# RK3562-DDR-PHY.net
KiCad netlist of a schematic drawn in Altium Designer
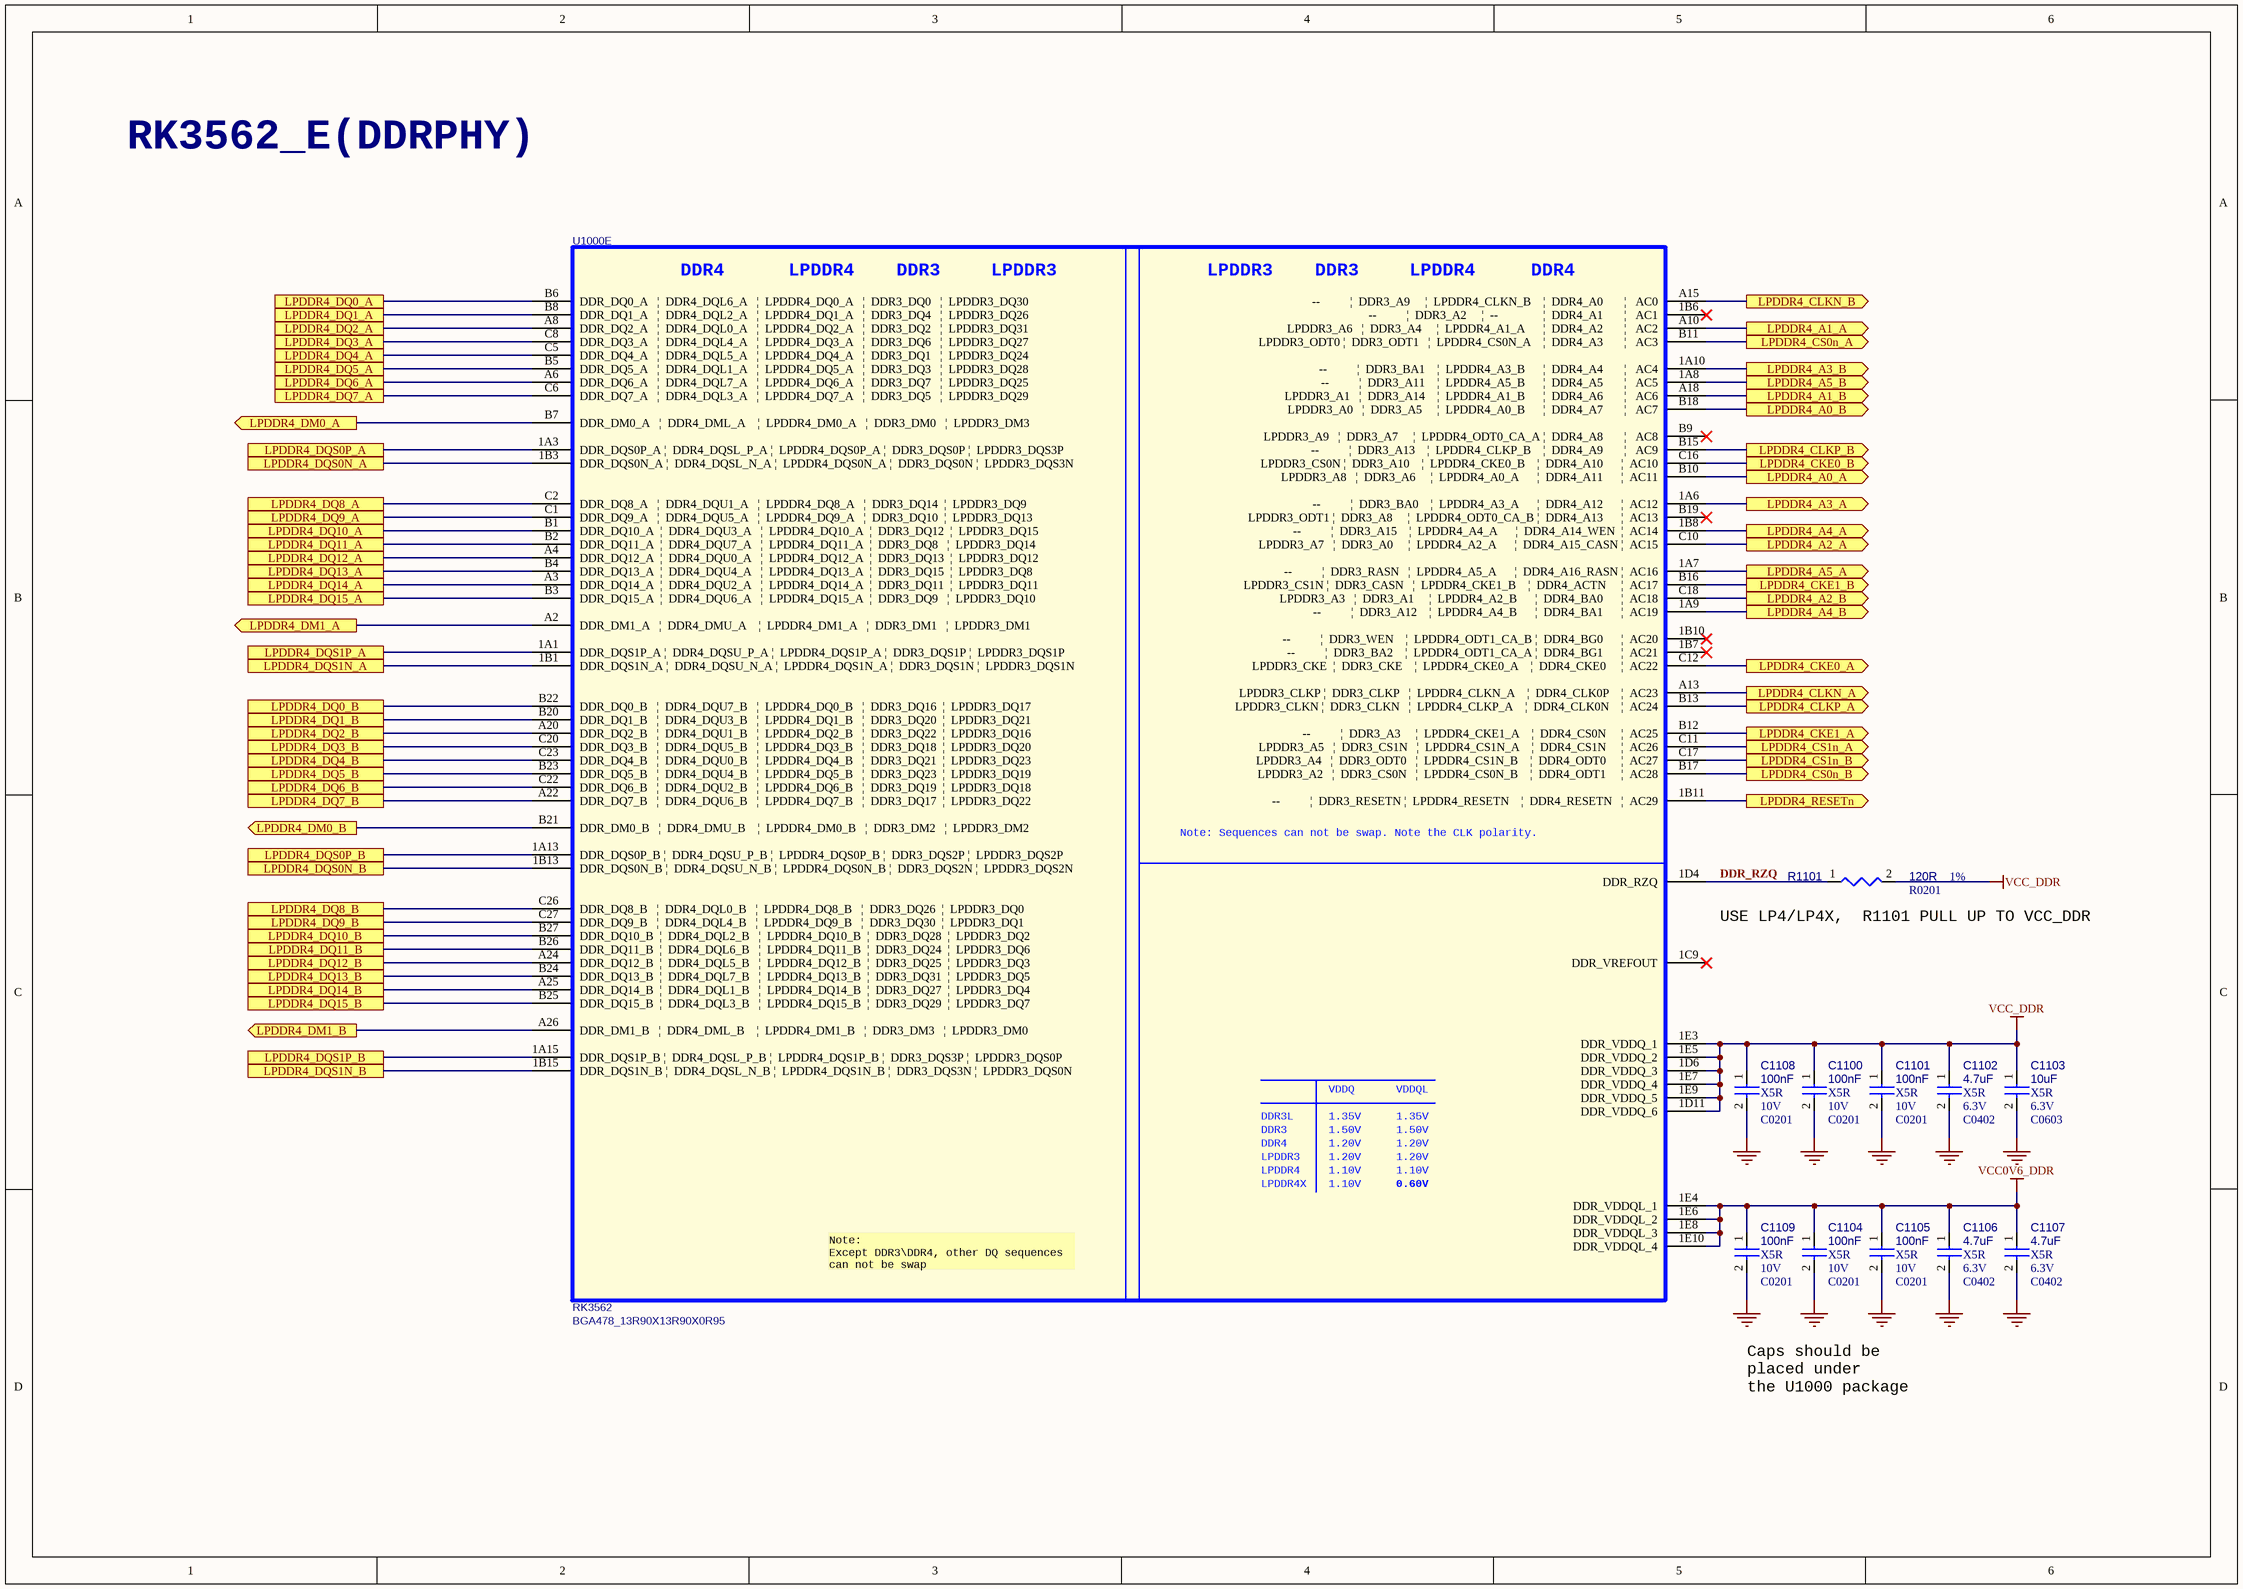
[diagram p0: RK3562-DDR-PHY.SchDoc]

(export (version "E")
  (design (tool "Eeschema 10.0.6"))
  (components
    (comp (ref "C1100")
      (value "100nF")
      (footprint "C0201")
      (description "cap,100.00nF,+/-10%,10V,X5R,C0201")
      (fields
        (field (name "DIELECTRIC") "X5R")
        (field (name "PCB FOOTPRINT") "C0201")
        (field (name "VOLTAGE") "10V")
        (field (name "MANUFACTURER") "TDK")
        (field (name "TOLERANCE") "10%")
        (field (name "CREATED BY") "JJJ")
      )
      (libsource (lib "RK3562_REF") (part "CAP NP"))
    )
    (comp (ref "C1101")
      (value "100nF")
      (footprint "C0201")
      (description "cap,100.00nF,+/-10%,10V,X5R,C0201")
      (fields
        (field (name "DIELECTRIC") "X5R")
        (field (name "PCB FOOTPRINT") "C0201")
        (field (name "VOLTAGE") "10V")
        (field (name "MANUFACTURER") "TDK")
        (field (name "TOLERANCE") "10%")
        (field (name "CREATED BY") "JJJ")
      )
      (libsource (lib "RK3562_REF") (part "CAP NP"))
    )
    (comp (ref "C1102")
      (value "4.7uF")
      (footprint "C0402")
      (description "cap,4.70uF,+/-10%,6.3V,X5R,C0402")
      (fields
        (field (name "DIELECTRIC") "X5R")
        (field (name "PCB FOOTPRINT") "C0402")
        (field (name "VOLTAGE") "6.3V")
        (field (name "TOLERANCE") "10%")
        (field (name "MANUFACTURER") "TDK")
        (field (name "CREATED BY") "JJJ")
      )
      (libsource (lib "RK3562_REF") (part "CAP NP"))
    )
    (comp (ref "C1103")
      (value "10uF")
      (footprint "C0603")
      (description "cap,10.00uF,+/-10%,6.3V,X5R,C0603")
      (fields
        (field (name "DIELECTRIC") "X5R")
        (field (name "PCB FOOTPRINT") "C0603")
        (field (name "VOLTAGE") "6.3V")
        (field (name "MANUFACTURER") "TDK")
        (field (name "TOLERANCE") "10%")
        (field (name "CREATED BY") "JJJ")
      )
      (libsource (lib "RK3562_REF") (part "CAP NP"))
    )
    (comp (ref "C1104")
      (value "100nF")
      (footprint "C0201")
      (description "cap,100.00nF,+/-10%,10V,X5R,C0201")
      (fields
        (field (name "DIELECTRIC") "X5R")
        (field (name "PCB FOOTPRINT") "C0201")
        (field (name "VOLTAGE") "10V")
        (field (name "MANUFACTURER") "TDK")
        (field (name "TOLERANCE") "10%")
        (field (name "CREATED BY") "JJJ")
      )
      (libsource (lib "RK3562_REF") (part "CAP NP"))
    )
    (comp (ref "C1105")
      (value "100nF")
      (footprint "C0201")
      (description "cap,100.00nF,+/-10%,10V,X5R,C0201")
      (fields
        (field (name "DIELECTRIC") "X5R")
        (field (name "PCB FOOTPRINT") "C0201")
        (field (name "VOLTAGE") "10V")
        (field (name "MANUFACTURER") "TDK")
        (field (name "TOLERANCE") "10%")
        (field (name "CREATED BY") "JJJ")
      )
      (libsource (lib "RK3562_REF") (part "CAP NP"))
    )
    (comp (ref "C1106")
      (value "4.7uF")
      (footprint "C0402")
      (description "cap,4.70uF,+/-10%,6.3V,X5R,C0402")
      (fields
        (field (name "DIELECTRIC") "X5R")
        (field (name "PCB FOOTPRINT") "C0402")
        (field (name "VOLTAGE") "6.3V")
        (field (name "TOLERANCE") "10%")
        (field (name "MANUFACTURER") "TDK")
        (field (name "CREATED BY") "JJJ")
      )
      (libsource (lib "RK3562_REF") (part "CAP NP"))
    )
    (comp (ref "C1107")
      (value "4.7uF")
      (footprint "C0402")
      (description "cap,4.70uF,+/-10%,6.3V,X5R,C0402")
      (fields
        (field (name "DIELECTRIC") "X5R")
        (field (name "PCB FOOTPRINT") "C0402")
        (field (name "VOLTAGE") "6.3V")
        (field (name "MANUFACTURER") "TDK")
        (field (name "TOLERANCE") "10%")
        (field (name "CREATED BY") "JJJ")
      )
      (libsource (lib "RK3562_REF") (part "CAP NP"))
    )
    (comp (ref "C1108")
      (value "100nF")
      (footprint "C0201")
      (description "cap,100.00nF,+/-10%,10V,X5R,C0201")
      (fields
        (field (name "DIELECTRIC") "X5R")
        (field (name "PCB FOOTPRINT") "C0201")
        (field (name "VOLTAGE") "10V")
        (field (name "TOLERANCE") "10%")
        (field (name "MANUFACTURER") "TDK")
        (field (name "CREATED BY") "JJJ")
      )
      (libsource (lib "RK3562_REF") (part "CAP NP"))
    )
    (comp (ref "C1109")
      (value "100nF")
      (footprint "C0201")
      (description "cap,100.00nF,+/-10%,10V,X5R,C0201")
      (fields
        (field (name "DIELECTRIC") "X5R")
        (field (name "PCB FOOTPRINT") "C0201")
        (field (name "VOLTAGE") "10V")
        (field (name "TOLERANCE") "10%")
        (field (name "MANUFACTURER") "TDK")
        (field (name "CREATED BY") "JJJ")
      )
      (libsource (lib "RK3562_REF") (part "CAP NP"))
    )
    (comp (ref "R1101")
      (value "120R")
      (footprint "R0201")
      (description "通用厚膜电阻,120R,+/-1%,R0201,1/20W.")
      (fields
        (field (name "TOLERANCE") "1%")
        (field (name "PCB FOOTPRINT") "R0201")
        (field (name "MANUFACTURER") "YAGEO")
        (field (name "CREATED BY") "YTL")
      )
      (libsource (lib "RK3562_REF") (part "RESISTOR"))
    )
    (comp (ref "U1000")
      (value "RK3562")
      (footprint "BGA478_13R90X13R90X0R95")
      (description "ROCKCHIP SOC")
      (fields
        (field (name "PCB FOOTPRINT") "BGA478_13R90X13R90X0R95")
        (field (name "MANUFACTURER") "Rockchip (瑞芯微)")
        (field (name "CREATED BY") "JJJ")
      )
      (libsource (lib "RK3562_REF") (part "SOC_RK3562"))
    )
  )
  (nets
    (net (code "1") (name "/DDR_RZQ") (class "Default")
      (node (ref "R1101") (pin "1") (pinfunction "1_1") (pintype "passive"))
      (node (ref "U1000") (pin "1D4") (pinfunction "DDR_RZQ_1D4") (pintype "passive"))
    )
    (net (code "2") (name "/LPDDR4_A0_A") (class "Default")
      (node (ref "U1000") (pin "B10") (pinfunction "LPDDR3_A8___¦__DDR3_A6_____¦__LPDDR4_A0_A______¦__DDR4_A11______¦__AC11_B10") (pintype "passive"))
    )
    (net (code "3") (name "/LPDDR4_A0_B") (class "Default")
      (node (ref "U1000") (pin "B18") (pinfunction "LPDDR3_A0___¦__DDR3_A5_____¦__LPDDR4_A0_B______¦__DDR4_A7_______¦___AC7_B18") (pintype "passive"))
    )
    (net (code "4") (name "/LPDDR4_A1_A") (class "Default")
      (node (ref "U1000") (pin "A10") (pinfunction "LPDDR3_A6___¦__DDR3_A4_____¦__LPDDR4_A1_A______¦__DDR4_A2_______¦___AC2_A10") (pintype "passive"))
    )
    (net (code "5") (name "/LPDDR4_A1_B") (class "Default")
      (node (ref "U1000") (pin "A18") (pinfunction "LPDDR3_A1___¦__DDR3_A14____¦__LPDDR4_A1_B______¦__DDR4_A6_______¦___AC6_A18") (pintype "passive"))
    )
    (net (code "6") (name "/LPDDR4_A2_A") (class "Default")
      (node (ref "U1000") (pin "C10") (pinfunction "LPDDR3_A7___¦__DDR3_A0_____¦__LPDDR4_A2_A______¦__DDR4_A15_CASN_¦__AC15_C10") (pintype "passive"))
    )
    (net (code "7") (name "/LPDDR4_A2_B") (class "Default")
      (node (ref "U1000") (pin "C18") (pinfunction "LPDDR3_A3___¦__DDR3_A1_____¦__LPDDR4_A2_B______¦__DDR4_BA0______¦__AC18_C18") (pintype "passive"))
    )
    (net (code "8") (name "/LPDDR4_A3_A") (class "Default")
      (node (ref "U1000") (pin "1A6") (pinfunction "--__________¦__DDR3_BA0____¦__LPDDR4_A3_A______¦__DDR4_A12______¦__AC12_1A6") (pintype "passive"))
    )
    (net (code "9") (name "/LPDDR4_A3_B") (class "Default")
      (node (ref "U1000") (pin "1A10") (pinfunction "--__________¦__DDR3_BA1____¦__LPDDR4_A3_B______¦__DDR4_A4_______¦___AC4_1A10") (pintype "passive"))
    )
    (net (code "10") (name "/LPDDR4_A4_A") (class "Default")
      (node (ref "U1000") (pin "1B8") (pinfunction "--__________¦__DDR3_A15____¦__LPDDR4_A4_A______¦__DDR4_A14_WEN__¦__AC14_1B8") (pintype "passive"))
    )
    (net (code "11") (name "/LPDDR4_A4_B") (class "Default")
      (node (ref "U1000") (pin "1A9") (pinfunction "--__________¦__DDR3_A12____¦__LPDDR4_A4_B______¦__DDR4_BA1______¦__AC19_1A9") (pintype "passive"))
    )
    (net (code "12") (name "/LPDDR4_A5_A") (class "Default")
      (node (ref "U1000") (pin "1A7") (pinfunction "--__________¦__DDR3_RASN___¦__LPDDR4_A5_A______¦__DDR4_A16_RASN_¦__AC16_1A7") (pintype "passive"))
    )
    (net (code "13") (name "/LPDDR4_A5_B") (class "Default")
      (node (ref "U1000") (pin "1A8") (pinfunction "--__________¦__DDR3_A11____¦__LPDDR4_A5_B______¦__DDR4_A5_______¦___AC5_1A8") (pintype "passive"))
    )
    (net (code "14") (name "/LPDDR4_CKE0_A") (class "Default")
      (node (ref "U1000") (pin "C12") (pinfunction "LPDDR3_CKE__¦__DDR3_CKE____¦__LPDDR4_CKE0_A____¦__DDR4_CKE0_____¦__AC22_C12") (pintype "passive"))
    )
    (net (code "15") (name "/LPDDR4_CKE0_B") (class "Default")
      (node (ref "U1000") (pin "C16") (pinfunction "LPDDR3_CS0N_¦__DDR3_A10____¦__LPDDR4_CKE0_B____¦__DDR4_A10______¦__AC10_C16") (pintype "passive"))
    )
    (net (code "16") (name "/LPDDR4_CKE1_A") (class "Default")
      (node (ref "U1000") (pin "B12") (pinfunction "--__________¦__DDR3_A3_____¦__LPDDR4_CKE1_A____¦__DDR4_CS0N_____¦__AC25_B12") (pintype "passive"))
    )
    (net (code "17") (name "/LPDDR4_CKE1_B") (class "Default")
      (node (ref "U1000") (pin "B16") (pinfunction "LPDDR3_CS1N_¦__DDR3_CASN___¦__LPDDR4_CKE1_B____¦__DDR4_ACTN_____¦__AC17_B16") (pintype "passive"))
    )
    (net (code "18") (name "/LPDDR4_CLKN_A") (class "Default")
      (node (ref "U1000") (pin "A13") (pinfunction "LPDDR3_CLKP_¦__DDR3_CLKP___¦__LPDDR4_CLKN_A____¦__DDR4_CLK0P____¦__AC23_A13") (pintype "passive"))
    )
    (net (code "19") (name "/LPDDR4_CLKN_B") (class "Default")
      (node (ref "U1000") (pin "A15") (pinfunction "--__________¦__DDR3_A9_____¦__LPDDR4_CLKN_B____¦__DDR4_A0_______¦___AC0_A15") (pintype "passive"))
    )
    (net (code "20") (name "/LPDDR4_CLKP_A") (class "Default")
      (node (ref "U1000") (pin "B13") (pinfunction "LPDDR3_CLKN_¦__DDR3_CLKN___¦__LPDDR4_CLKP_A____¦__DDR4_CLK0N____¦__AC24_B13") (pintype "passive"))
    )
    (net (code "21") (name "/LPDDR4_CLKP_B") (class "Default")
      (node (ref "U1000") (pin "B15") (pinfunction "--__________¦__DDR3_A13____¦__LPDDR4_CLKP_B____¦__DDR4_A9_______¦___AC9_B15") (pintype "passive"))
    )
    (net (code "22") (name "/LPDDR4_CS0n_A") (class "Default")
      (node (ref "U1000") (pin "B11") (pinfunction "LPDDR3_ODT0_¦__DDR3_ODT1___¦__LPDDR4_CS0N_A____¦__DDR4_A3_______¦___AC3_B11") (pintype "passive"))
    )
    (net (code "23") (name "/LPDDR4_CS0n_B") (class "Default")
      (node (ref "U1000") (pin "B17") (pinfunction "LPDDR3_A2___¦__DDR3_CS0N___¦__LPDDR4_CS0N_B____¦__DDR4_ODT1_____¦__AC28_B17") (pintype "passive"))
    )
    (net (code "24") (name "/LPDDR4_CS1n_A") (class "Default")
      (node (ref "U1000") (pin "C11") (pinfunction "LPDDR3_A5___¦__DDR3_CS1N___¦__LPDDR4_CS1N_A____¦__DDR4_CS1N_____¦__AC26_C11") (pintype "passive"))
    )
    (net (code "25") (name "/LPDDR4_CS1n_B") (class "Default")
      (node (ref "U1000") (pin "C17") (pinfunction "LPDDR3_A4___¦__DDR3_ODT0___¦__LPDDR4_CS1N_B____¦__DDR4_ODT0_____¦__AC27_C17") (pintype "passive"))
    )
    (net (code "26") (name "/LPDDR4_DM0_A") (class "Default")
      (node (ref "U1000") (pin "B7") (pinfunction "DDR_DM0_A___¦__DDR4_DML_A____¦__LPDDR4_DM0_A___¦__DDR3_DM0___¦__LPDDR3_DM3_B7") (pintype "passive"))
    )
    (net (code "27") (name "/LPDDR4_DM0_B") (class "Default")
      (node (ref "U1000") (pin "B21") (pinfunction "DDR_DM0_B___¦__DDR4_DMU_B____¦__LPDDR4_DM0_B___¦__DDR3_DM2___¦__LPDDR3_DM2_B21") (pintype "passive"))
    )
    (net (code "28") (name "/LPDDR4_DM1_A") (class "Default")
      (node (ref "U1000") (pin "A2") (pinfunction "DDR_DM1_A___¦__DDR4_DMU_A____¦__LPDDR4_DM1_A___¦__DDR3_DM1___¦__LPDDR3_DM1_A2") (pintype "passive"))
    )
    (net (code "29") (name "/LPDDR4_DM1_B") (class "Default")
      (node (ref "U1000") (pin "A26") (pinfunction "DDR_DM1_B___¦__DDR4_DML_B____¦__LPDDR4_DM1_B___¦__DDR3_DM3___¦__LPDDR3_DM0_A26") (pintype "passive"))
    )
    (net (code "30") (name "/LPDDR4_DQ0_A") (class "Default")
      (node (ref "U1000") (pin "B6") (pinfunction "DDR_DQ0_A___¦__DDR4_DQL6_A___¦__LPDDR4_DQ0_A___¦__DDR3_DQ0___¦__LPDDR3_DQ30_B6") (pintype "passive"))
    )
    (net (code "31") (name "/LPDDR4_DQ0_B") (class "Default")
      (node (ref "U1000") (pin "B22") (pinfunction "DDR_DQ0_B___¦__DDR4_DQU7_B___¦__LPDDR4_DQ0_B___¦__DDR3_DQ16__¦__LPDDR3_DQ17_B22") (pintype "passive"))
    )
    (net (code "32") (name "/LPDDR4_DQ1_A") (class "Default")
      (node (ref "U1000") (pin "B8") (pinfunction "DDR_DQ1_A___¦__DDR4_DQL2_A___¦__LPDDR4_DQ1_A___¦__DDR3_DQ4___¦__LPDDR3_DQ26_B8") (pintype "passive"))
    )
    (net (code "33") (name "/LPDDR4_DQ1_B") (class "Default")
      (node (ref "U1000") (pin "B20") (pinfunction "DDR_DQ1_B___¦__DDR4_DQU3_B___¦__LPDDR4_DQ1_B___¦__DDR3_DQ20__¦__LPDDR3_DQ21_B20") (pintype "passive"))
    )
    (net (code "34") (name "/LPDDR4_DQ2_A") (class "Default")
      (node (ref "U1000") (pin "A8") (pinfunction "DDR_DQ2_A___¦__DDR4_DQL0_A___¦__LPDDR4_DQ2_A___¦__DDR3_DQ2___¦__LPDDR3_DQ31_A8") (pintype "passive"))
    )
    (net (code "35") (name "/LPDDR4_DQ2_B") (class "Default")
      (node (ref "U1000") (pin "A20") (pinfunction "DDR_DQ2_B___¦__DDR4_DQU1_B___¦__LPDDR4_DQ2_B___¦__DDR3_DQ22__¦__LPDDR3_DQ16_A20") (pintype "passive"))
    )
    (net (code "36") (name "/LPDDR4_DQ3_A") (class "Default")
      (node (ref "U1000") (pin "C8") (pinfunction "DDR_DQ3_A___¦__DDR4_DQL4_A___¦__LPDDR4_DQ3_A___¦__DDR3_DQ6___¦__LPDDR3_DQ27_C8") (pintype "passive"))
    )
    (net (code "37") (name "/LPDDR4_DQ3_B") (class "Default")
      (node (ref "U1000") (pin "C20") (pinfunction "DDR_DQ3_B___¦__DDR4_DQU5_B___¦__LPDDR4_DQ3_B___¦__DDR3_DQ18__¦__LPDDR3_DQ20_C20") (pintype "passive"))
    )
    (net (code "38") (name "/LPDDR4_DQ4_A") (class "Default")
      (node (ref "U1000") (pin "C5") (pinfunction "DDR_DQ4_A___¦__DDR4_DQL5_A___¦__LPDDR4_DQ4_A___¦__DDR3_DQ1___¦__LPDDR3_DQ24_C5") (pintype "passive"))
    )
    (net (code "39") (name "/LPDDR4_DQ4_B") (class "Default")
      (node (ref "U1000") (pin "C23") (pinfunction "DDR_DQ4_B___¦__DDR4_DQU0_B___¦__LPDDR4_DQ4_B___¦__DDR3_DQ21__¦__LPDDR3_DQ23_C23") (pintype "passive"))
    )
    (net (code "40") (name "/LPDDR4_DQ5_A") (class "Default")
      (node (ref "U1000") (pin "B5") (pinfunction "DDR_DQ5_A___¦__DDR4_DQL1_A___¦__LPDDR4_DQ5_A___¦__DDR3_DQ3___¦__LPDDR3_DQ28_B5") (pintype "passive"))
    )
    (net (code "41") (name "/LPDDR4_DQ5_B") (class "Default")
      (node (ref "U1000") (pin "B23") (pinfunction "DDR_DQ5_B___¦__DDR4_DQU4_B___¦__LPDDR4_DQ5_B___¦__DDR3_DQ23__¦__LPDDR3_DQ19_B23") (pintype "passive"))
    )
    (net (code "42") (name "/LPDDR4_DQ6_A") (class "Default")
      (node (ref "U1000") (pin "A6") (pinfunction "DDR_DQ6_A___¦__DDR4_DQL7_A___¦__LPDDR4_DQ6_A___¦__DDR3_DQ7___¦__LPDDR3_DQ25_A6") (pintype "passive"))
    )
    (net (code "43") (name "/LPDDR4_DQ6_B") (class "Default")
      (node (ref "U1000") (pin "C22") (pinfunction "DDR_DQ6_B___¦__DDR4_DQU2_B___¦__LPDDR4_DQ6_B___¦__DDR3_DQ19__¦__LPDDR3_DQ18_C22") (pintype "passive"))
    )
    (net (code "44") (name "/LPDDR4_DQ7_A") (class "Default")
      (node (ref "U1000") (pin "C6") (pinfunction "DDR_DQ7_A___¦__DDR4_DQL3_A___¦__LPDDR4_DQ7_A___¦__DDR3_DQ5___¦__LPDDR3_DQ29_C6") (pintype "passive"))
    )
    (net (code "45") (name "/LPDDR4_DQ7_B") (class "Default")
      (node (ref "U1000") (pin "A22") (pinfunction "DDR_DQ7_B___¦__DDR4_DQU6_B___¦__LPDDR4_DQ7_B___¦__DDR3_DQ17__¦__LPDDR3_DQ22_A22") (pintype "passive"))
    )
    (net (code "46") (name "/LPDDR4_DQ8_A") (class "Default")
      (node (ref "U1000") (pin "C2") (pinfunction "DDR_DQ8_A___¦__DDR4_DQU1_A___¦__LPDDR4_DQ8_A___¦__DDR3_DQ14__¦__LPDDR3_DQ9_C2") (pintype "passive"))
    )
    (net (code "47") (name "/LPDDR4_DQ8_B") (class "Default")
      (node (ref "U1000") (pin "C26") (pinfunction "DDR_DQ8_B___¦__DDR4_DQL0_B___¦__LPDDR4_DQ8_B___¦__DDR3_DQ26__¦__LPDDR3_DQ0_C26") (pintype "passive"))
    )
    (net (code "48") (name "/LPDDR4_DQ9_A") (class "Default")
      (node (ref "U1000") (pin "C1") (pinfunction "DDR_DQ9_A___¦__DDR4_DQU5_A___¦__LPDDR4_DQ9_A___¦__DDR3_DQ10__¦__LPDDR3_DQ13_C1") (pintype "passive"))
    )
    (net (code "49") (name "/LPDDR4_DQ9_B") (class "Default")
      (node (ref "U1000") (pin "C27") (pinfunction "DDR_DQ9_B___¦__DDR4_DQL4_B___¦__LPDDR4_DQ9_B___¦__DDR3_DQ30__¦__LPDDR3_DQ1_C27") (pintype "passive"))
    )
    (net (code "50") (name "/LPDDR4_DQ10_A") (class "Default")
      (node (ref "U1000") (pin "B1") (pinfunction "DDR_DQ10_A__¦__DDR4_DQU3_A___¦__LPDDR4_DQ10_A__¦__DDR3_DQ12__¦__LPDDR3_DQ15_B1") (pintype "passive"))
    )
    (net (code "51") (name "/LPDDR4_DQ10_B") (class "Default")
      (node (ref "U1000") (pin "B27") (pinfunction "DDR_DQ10_B__¦__DDR4_DQL2_B___¦__LPDDR4_DQ10_B__¦__DDR3_DQ28__¦__LPDDR3_DQ2_B27") (pintype "passive"))
    )
    (net (code "52") (name "/LPDDR4_DQ11_A") (class "Default")
      (node (ref "U1000") (pin "B2") (pinfunction "DDR_DQ11_A__¦__DDR4_DQU7_A___¦__LPDDR4_DQ11_A__¦__DDR3_DQ8___¦__LPDDR3_DQ14_B2") (pintype "passive"))
    )
    (net (code "53") (name "/LPDDR4_DQ11_B") (class "Default")
      (node (ref "U1000") (pin "B26") (pinfunction "DDR_DQ11_B__¦__DDR4_DQL6_B___¦__LPDDR4_DQ11_B__¦__DDR3_DQ24__¦__LPDDR3_DQ6_B26") (pintype "passive"))
    )
    (net (code "54") (name "/LPDDR4_DQ12_A") (class "Default")
      (node (ref "U1000") (pin "A4") (pinfunction "DDR_DQ12_A__¦__DDR4_DQU0_A___¦__LPDDR4_DQ12_A__¦__DDR3_DQ13__¦__LPDDR3_DQ12_A4") (pintype "passive"))
    )
    (net (code "55") (name "/LPDDR4_DQ12_B") (class "Default")
      (node (ref "U1000") (pin "A24") (pinfunction "DDR_DQ12_B__¦__DDR4_DQL5_B___¦__LPDDR4_DQ12_B__¦__DDR3_DQ25__¦__LPDDR3_DQ3_A24") (pintype "passive"))
    )
    (net (code "56") (name "/LPDDR4_DQ13_A") (class "Default")
      (node (ref "U1000") (pin "B4") (pinfunction "DDR_DQ13_A__¦__DDR4_DQU4_A___¦__LPDDR4_DQ13_A__¦__DDR3_DQ15__¦__LPDDR3_DQ8_B4") (pintype "passive"))
    )
    (net (code "57") (name "/LPDDR4_DQ13_B") (class "Default")
      (node (ref "U1000") (pin "B24") (pinfunction "DDR_DQ13_B__¦__DDR4_DQL7_B___¦__LPDDR4_DQ13_B__¦__DDR3_DQ31__¦__LPDDR3_DQ5_B24") (pintype "passive"))
    )
    (net (code "58") (name "/LPDDR4_DQ14_A") (class "Default")
      (node (ref "U1000") (pin "A3") (pinfunction "DDR_DQ14_A__¦__DDR4_DQU2_A___¦__LPDDR4_DQ14_A__¦__DDR3_DQ11__¦__LPDDR3_DQ11_A3") (pintype "passive"))
    )
    (net (code "59") (name "/LPDDR4_DQ14_B") (class "Default")
      (node (ref "U1000") (pin "A25") (pinfunction "DDR_DQ14_B__¦__DDR4_DQL1_B___¦__LPDDR4_DQ14_B__¦__DDR3_DQ27__¦__LPDDR3_DQ4_A25") (pintype "passive"))
    )
    (net (code "60") (name "/LPDDR4_DQ15_A") (class "Default")
      (node (ref "U1000") (pin "B3") (pinfunction "DDR_DQ15_A__¦__DDR4_DQU6_A___¦__LPDDR4_DQ15_A__¦__DDR3_DQ9___¦__LPDDR3_DQ10_B3") (pintype "passive"))
    )
    (net (code "61") (name "/LPDDR4_DQ15_B") (class "Default")
      (node (ref "U1000") (pin "B25") (pinfunction "DDR_DQ15_B__¦__DDR4_DQL3_B___¦__LPDDR4_DQ15_B__¦__DDR3_DQ29__¦__LPDDR3_DQ7_B25") (pintype "passive"))
    )
    (net (code "62") (name "/LPDDR4_DQS0N_A") (class "Default")
      (node (ref "U1000") (pin "1B3") (pinfunction "DDR_DQS0N_A_¦__DDR4_DQSL_N_A_¦__LPDDR4_DQS0N_A_¦__DDR3_DQS0N_¦__LPDDR3_DQS3N_1B3") (pintype "passive"))
    )
    (net (code "63") (name "/LPDDR4_DQS0N_B") (class "Default")
      (node (ref "U1000") (pin "1B13") (pinfunction "DDR_DQS0N_B_¦__DDR4_DQSU_N_B_¦__LPDDR4_DQS0N_B_¦__DDR3_DQS2N_¦__LPDDR3_DQS2N_1B13") (pintype "passive"))
    )
    (net (code "64") (name "/LPDDR4_DQS0P_A") (class "Default")
      (node (ref "U1000") (pin "1A3") (pinfunction "DDR_DQS0P_A_¦__DDR4_DQSL_P_A_¦__LPDDR4_DQS0P_A_¦__DDR3_DQS0P_¦__LPDDR3_DQS3P_1A3") (pintype "passive"))
    )
    (net (code "65") (name "/LPDDR4_DQS0P_B") (class "Default")
      (node (ref "U1000") (pin "1A13") (pinfunction "DDR_DQS0P_B_¦__DDR4_DQSU_P_B_¦__LPDDR4_DQS0P_B_¦__DDR3_DQS2P_¦__LPDDR3_DQS2P_1A13") (pintype "passive"))
    )
    (net (code "66") (name "/LPDDR4_DQS1N_A") (class "Default")
      (node (ref "U1000") (pin "1B1") (pinfunction "DDR_DQS1N_A_¦__DDR4_DQSU_N_A_¦__LPDDR4_DQS1N_A_¦__DDR3_DQS1N_¦__LPDDR3_DQS1N_1B1") (pintype "passive"))
    )
    (net (code "67") (name "/LPDDR4_DQS1N_B") (class "Default")
      (node (ref "U1000") (pin "1B15") (pinfunction "DDR_DQS1N_B_¦__DDR4_DQSL_N_B_¦__LPDDR4_DQS1N_B_¦__DDR3_DQS3N_¦__LPDDR3_DQS0N_1B15") (pintype "passive"))
    )
    (net (code "68") (name "/LPDDR4_DQS1P_A") (class "Default")
      (node (ref "U1000") (pin "1A1") (pinfunction "DDR_DQS1P_A_¦__DDR4_DQSU_P_A_¦__LPDDR4_DQS1P_A_¦__DDR3_DQS1P_¦__LPDDR3_DQS1P_1A1") (pintype "passive"))
    )
    (net (code "69") (name "/LPDDR4_DQS1P_B") (class "Default")
      (node (ref "U1000") (pin "1A15") (pinfunction "DDR_DQS1P_B_¦__DDR4_DQSL_P_B_¦__LPDDR4_DQS1P_B_¦__DDR3_DQS3P_¦__LPDDR3_DQS0P_1A15") (pintype "passive"))
    )
    (net (code "70") (name "/LPDDR4_RESETn") (class "Default")
      (node (ref "U1000") (pin "1B11") (pinfunction "--__________¦__DDR3_RESETN_¦__LPDDR4_RESETN____¦__DDR4_RESETN___¦__AC29_1B11") (pintype "passive"))
    )
    (net (code "71") (name "GND") (class "Default")
      (node (ref "C1100") (pin "2") (pinfunction "2_2") (pintype "passive"))
      (node (ref "C1101") (pin "2") (pinfunction "2_2") (pintype "passive"))
      (node (ref "C1102") (pin "2") (pinfunction "2_2") (pintype "passive"))
      (node (ref "C1103") (pin "2") (pinfunction "2_2") (pintype "passive"))
      (node (ref "C1104") (pin "2") (pinfunction "2_2") (pintype "passive"))
      (node (ref "C1105") (pin "2") (pinfunction "2_2") (pintype "passive"))
      (node (ref "C1106") (pin "2") (pinfunction "2_2") (pintype "passive"))
      (node (ref "C1107") (pin "2") (pinfunction "2_2") (pintype "passive"))
      (node (ref "C1108") (pin "2") (pinfunction "2_2") (pintype "passive"))
      (node (ref "C1109") (pin "2") (pinfunction "2_2") (pintype "passive"))
    )
    (net (code "72") (name "VCC0V6_DDR") (class "Default")
      (node (ref "C1104") (pin "1") (pinfunction "1_1") (pintype "passive"))
      (node (ref "C1105") (pin "1") (pinfunction "1_1") (pintype "passive"))
      (node (ref "C1106") (pin "1") (pinfunction "1_1") (pintype "passive"))
      (node (ref "C1107") (pin "1") (pinfunction "1_1") (pintype "passive"))
      (node (ref "C1109") (pin "1") (pinfunction "1_1") (pintype "passive"))
      (node (ref "U1000") (pin "1E10") (pinfunction "DDR_VDDQL_4_1E10") (pintype "passive"))
      (node (ref "U1000") (pin "1E4") (pinfunction "DDR_VDDQL_1_1E4") (pintype "passive"))
      (node (ref "U1000") (pin "1E6") (pinfunction "DDR_VDDQL_2_1E6") (pintype "passive"))
      (node (ref "U1000") (pin "1E8") (pinfunction "DDR_VDDQL_3_1E8") (pintype "passive"))
    )
    (net (code "73") (name "VCC_DDR") (class "Default")
      (node (ref "C1100") (pin "1") (pinfunction "1_1") (pintype "passive"))
      (node (ref "C1101") (pin "1") (pinfunction "1_1") (pintype "passive"))
      (node (ref "C1102") (pin "1") (pinfunction "1_1") (pintype "passive"))
      (node (ref "C1103") (pin "1") (pinfunction "1_1") (pintype "passive"))
      (node (ref "C1108") (pin "1") (pinfunction "1_1") (pintype "passive"))
      (node (ref "R1101") (pin "2") (pinfunction "2_2") (pintype "passive"))
      (node (ref "U1000") (pin "1D11") (pinfunction "DDR_VDDQ_6_1D11") (pintype "passive"))
      (node (ref "U1000") (pin "1D6") (pinfunction "DDR_VDDQ_3_1D6") (pintype "passive"))
      (node (ref "U1000") (pin "1E3") (pinfunction "DDR_VDDQ_1_1E3") (pintype "passive"))
      (node (ref "U1000") (pin "1E5") (pinfunction "DDR_VDDQ_2_1E5") (pintype "passive"))
      (node (ref "U1000") (pin "1E7") (pinfunction "DDR_VDDQ_4_1E7") (pintype "passive"))
      (node (ref "U1000") (pin "1E9") (pinfunction "DDR_VDDQ_5_1E9") (pintype "passive"))
    )
    (net (code "74") (name "unconnected-(U1000E---__________¦__DDR3_A2_____¦__--_______________¦__DDR4_A1_______¦___AC1-Pad1B6)") (class "Default")
      (node (ref "U1000") (pin "1B6") (pinfunction "--__________¦__DDR3_A2_____¦__--_______________¦__DDR4_A1_______¦___AC1_1B6") (pintype "passive+no_connect"))
    )
    (net (code "75") (name "unconnected-(U1000E---__________¦__DDR3_BA2____¦__LPDDR4_ODT1_CA_A_¦__DDR4_BG1______¦__AC21-Pad1B7)") (class "Default")
      (node (ref "U1000") (pin "1B7") (pinfunction "--__________¦__DDR3_BA2____¦__LPDDR4_ODT1_CA_A_¦__DDR4_BG1______¦__AC21_1B7") (pintype "passive+no_connect"))
    )
    (net (code "76") (name "unconnected-(U1000E---__________¦__DDR3_WEN____¦__LPDDR4_ODT1_CA_B_¦__DDR4_BG0______¦__AC20-Pad1B10)") (class "Default")
      (node (ref "U1000") (pin "1B10") (pinfunction "--__________¦__DDR3_WEN____¦__LPDDR4_ODT1_CA_B_¦__DDR4_BG0______¦__AC20_1B10") (pintype "passive+no_connect"))
    )
    (net (code "77") (name "unconnected-(U1000E-DDR_VREFOUT-Pad1C9)") (class "Default")
      (node (ref "U1000") (pin "1C9") (pinfunction "DDR_VREFOUT_1C9") (pintype "passive+no_connect"))
    )
    (net (code "78") (name "unconnected-(U1000E-LPDDR3_A9___¦__DDR3_A7_____¦__LPDDR4_ODT0_CA_A_¦__DDR4_A8_______¦___AC8-PadB9)") (class "Default")
      (node (ref "U1000") (pin "B9") (pinfunction "LPDDR3_A9___¦__DDR3_A7_____¦__LPDDR4_ODT0_CA_A_¦__DDR4_A8_______¦___AC8_B9") (pintype "passive+no_connect"))
    )
    (net (code "79") (name "unconnected-(U1000E-LPDDR3_ODT1_¦__DDR3_A8_____¦__LPDDR4_ODT0_CA_B_¦__DDR4_A13______¦__AC13-PadB19)") (class "Default")
      (node (ref "U1000") (pin "B19") (pinfunction "LPDDR3_ODT1_¦__DDR3_A8_____¦__LPDDR4_ODT0_CA_B_¦__DDR4_A13______¦__AC13_B19") (pintype "passive+no_connect"))
    )
  )
)
